# motorized_potentiometer.net
KiCad netlist of a schematic drawn in EAGLE
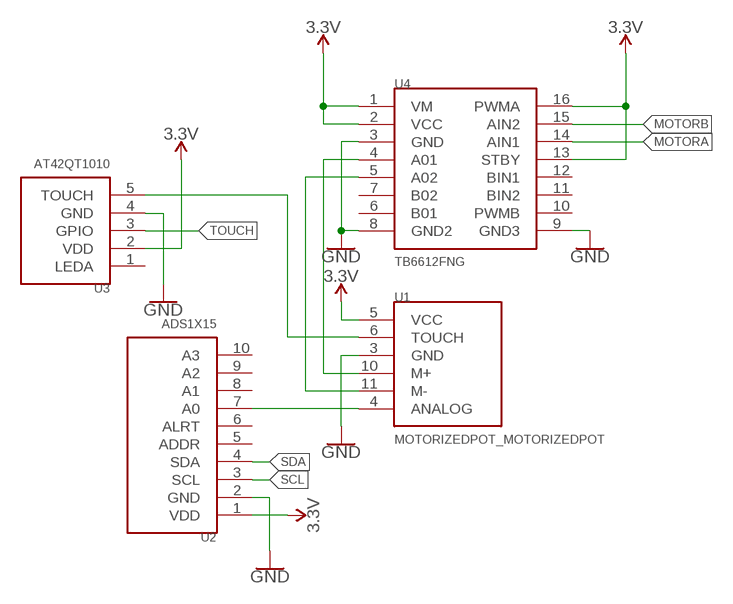
[diagram p0: schematic, sheet 1]

(export (version "E")
  (design (tool "Eeschema 10.0.6"))
  (components
    (comp (ref "U1")
      (value "MOTORIZEDPOT_MOTORIZEDPOT")
      (footprint "eagle-import:MOTORIZEDPOT_MOTORIZEDPOT")
      (libsource (lib "eagle-import") (part "MOTORIZEDPOT_MOTORIZEDPOT"))
    )
    (comp (ref "U2")
      (value "ADS1X15")
      (footprint "eagle-import:ADS1X15")
      (libsource (lib "eagle-import") (part "ADS1X15"))
    )
    (comp (ref "U3")
      (value "AT42QT1010")
      (footprint "eagle-import:AT42QT1010")
      (libsource (lib "eagle-import") (part "AT42QT1010"))
    )
    (comp (ref "U4")
      (value "TB6612FNG")
      (footprint "eagle-import:TB6612FNG")
      (libsource (lib "eagle-import") (part "TB6612FNG"))
    )
  )
  (nets
    (net (code "1") (name "3.3V") (class "Default")
      (node (ref "U1") (pin "5") (pinfunction "VCC_5") (pintype "bidirectional"))
      (node (ref "U2") (pin "1") (pinfunction "VDD_1") (pintype "bidirectional"))
      (node (ref "U3") (pin "2") (pinfunction "VDD_2") (pintype "bidirectional"))
      (node (ref "U4") (pin "1") (pinfunction "VM_1") (pintype "bidirectional"))
      (node (ref "U4") (pin "13") (pinfunction "STBY_13") (pintype "bidirectional"))
      (node (ref "U4") (pin "16") (pinfunction "PWMA_16") (pintype "bidirectional"))
      (node (ref "U4") (pin "2") (pinfunction "VCC_2") (pintype "bidirectional"))
    )
    (net (code "2") (name "GND") (class "Default")
      (node (ref "U1") (pin "3") (pinfunction "GND_3") (pintype "bidirectional"))
      (node (ref "U2") (pin "2") (pinfunction "GND_2") (pintype "bidirectional"))
      (node (ref "U3") (pin "4") (pinfunction "GND_4") (pintype "bidirectional"))
      (node (ref "U4") (pin "3") (pinfunction "GND_3") (pintype "bidirectional"))
      (node (ref "U4") (pin "8") (pinfunction "GND2_8") (pintype "bidirectional"))
      (node (ref "U4") (pin "9") (pinfunction "GND3_9") (pintype "bidirectional"))
    )
    (net (code "3") (name "MOTORA") (class "Default")
      (node (ref "U4") (pin "14") (pinfunction "AIN1_14") (pintype "bidirectional"))
    )
    (net (code "4") (name "MOTORB") (class "Default")
      (node (ref "U4") (pin "15") (pinfunction "AIN2_15") (pintype "bidirectional"))
    )
    (net (code "5") (name "Net-(U1-ANALOG)") (class "Default")
      (node (ref "U1") (pin "4") (pinfunction "ANALOG_4") (pintype "bidirectional"))
      (node (ref "U2") (pin "7") (pinfunction "A0_7") (pintype "bidirectional"))
    )
    (net (code "6") (name "Net-(U1-M+)") (class "Default")
      (node (ref "U1") (pin "10") (pinfunction "M+_10") (pintype "bidirectional"))
      (node (ref "U4") (pin "4") (pinfunction "A01_4") (pintype "bidirectional"))
    )
    (net (code "7") (name "Net-(U1-M-)") (class "Default")
      (node (ref "U1") (pin "11") (pinfunction "M-_11") (pintype "bidirectional"))
      (node (ref "U4") (pin "5") (pinfunction "A02_5") (pintype "bidirectional"))
    )
    (net (code "8") (name "Net-(U1-TOUCH)") (class "Default")
      (node (ref "U1") (pin "6") (pinfunction "TOUCH_6") (pintype "bidirectional"))
      (node (ref "U3") (pin "5") (pinfunction "TOUCH_5") (pintype "bidirectional"))
    )
    (net (code "9") (name "SCL") (class "Default")
      (node (ref "U2") (pin "3") (pinfunction "SCL_3") (pintype "bidirectional"))
    )
    (net (code "10") (name "SDA") (class "Default")
      (node (ref "U2") (pin "4") (pinfunction "SDA_4") (pintype "bidirectional"))
    )
    (net (code "11") (name "TOUCH") (class "Default")
      (node (ref "U3") (pin "3") (pinfunction "GPIO_3") (pintype "bidirectional"))
    )
    (net (code "12") (name "unconnected-(U2-A1-Pad8)") (class "Default")
      (node (ref "U2") (pin "8") (pinfunction "A1_8") (pintype "bidirectional"))
    )
    (net (code "13") (name "unconnected-(U2-A2-Pad9)") (class "Default")
      (node (ref "U2") (pin "9") (pinfunction "A2_9") (pintype "bidirectional"))
    )
    (net (code "14") (name "unconnected-(U2-A3-Pad10)") (class "Default")
      (node (ref "U2") (pin "10") (pinfunction "A3_10") (pintype "bidirectional"))
    )
    (net (code "15") (name "unconnected-(U2-ADDR-Pad5)") (class "Default")
      (node (ref "U2") (pin "5") (pinfunction "ADDR_5") (pintype "bidirectional"))
    )
    (net (code "16") (name "unconnected-(U2-ALRT-Pad6)") (class "Default")
      (node (ref "U2") (pin "6") (pinfunction "ALRT_6") (pintype "bidirectional"))
    )
    (net (code "17") (name "unconnected-(U3-LEDA-Pad1)") (class "Default")
      (node (ref "U3") (pin "1") (pinfunction "LEDA_1") (pintype "bidirectional"))
    )
    (net (code "18") (name "unconnected-(U4-B01-Pad6)") (class "Default")
      (node (ref "U4") (pin "6") (pinfunction "B01_6") (pintype "bidirectional"))
    )
    (net (code "19") (name "unconnected-(U4-B02-Pad7)") (class "Default")
      (node (ref "U4") (pin "7") (pinfunction "B02_7") (pintype "bidirectional"))
    )
    (net (code "20") (name "unconnected-(U4-BIN1-Pad12)") (class "Default")
      (node (ref "U4") (pin "12") (pinfunction "BIN1_12") (pintype "bidirectional"))
    )
    (net (code "21") (name "unconnected-(U4-BIN2-Pad11)") (class "Default")
      (node (ref "U4") (pin "11") (pinfunction "BIN2_11") (pintype "bidirectional"))
    )
    (net (code "22") (name "unconnected-(U4-PWMB-Pad10)") (class "Default")
      (node (ref "U4") (pin "10") (pinfunction "PWMB_10") (pintype "bidirectional"))
    )
  )
)
